# breakout.net
KiCad netlist of a schematic drawn in Altium Designer
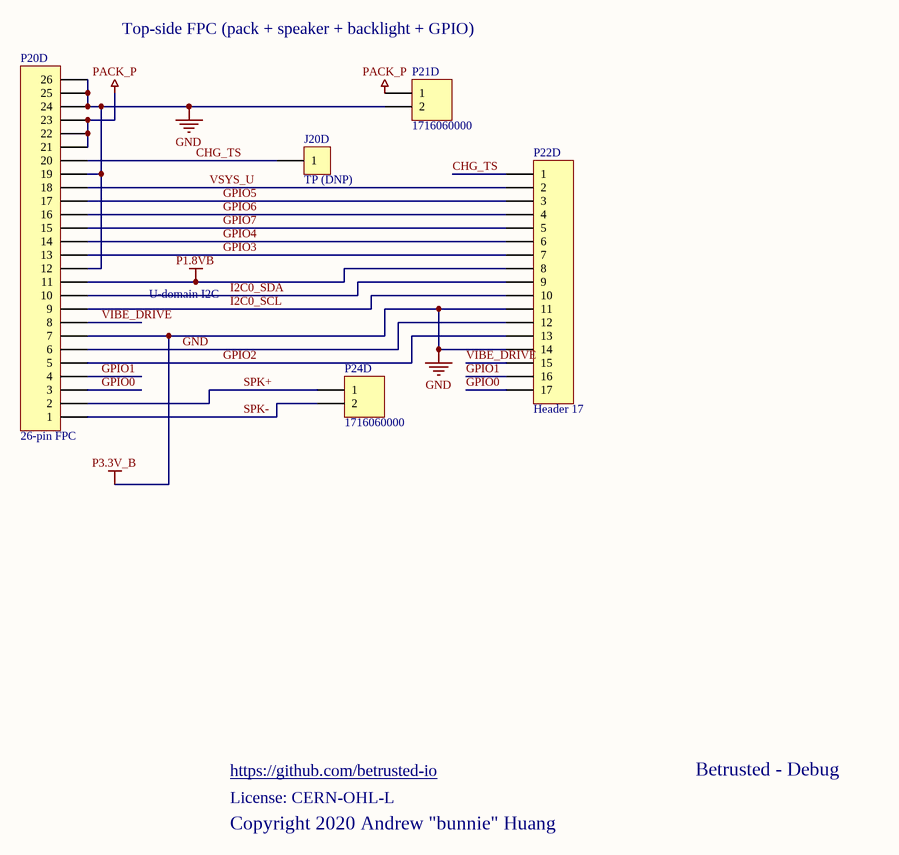
[diagram p0: breakout.SchDoc]

(export (version "E")
  (design (tool "Eeschema 10.0.6"))
  (components
    (comp (ref "J20D")
      (value "TP (DNP)")
      (footprint "RESTAP-0603")
      (description "Connector")
      (fields (field (name "MPN") "DNP"))
      (libsource (lib "*") (part "CON1"))
    )
    (comp (ref "P20D")
      (value "26-pin FPC")
      (footprint "HRS_FH34SRJ-26S-0.5SH(50)")
      (description "26 Pin FPC header")
      (fields (field (name "MPN") "FH34SRJ-26S-0.5SH(99)"))
      (libsource (lib "commonsch-new") (part "FPC-26"))
    )
    (comp (ref "P21D")
      (value "1716060000")
      (footprint "weidmuller_1716060000")
      (description "Header, 2-Pin")
      (fields (field (name "PUBLISHER") "Altium Limited"))
      (libsource (lib "Miscellaneous Connectors") (part "Header 2"))
    )
    (comp (ref "P22D")
      (value "Header 17")
      (footprint "HDR1X17")
      (description "Header, 17-Pin")
      (fields (field (name "PUBLISHER") "Altium Limited"))
      (libsource (lib "Miscellaneous Connectors") (part "Header 17"))
    )
    (comp (ref "P24D")
      (value "1716060000")
      (footprint "weidmuller_1716060000")
      (description "Header, 2-Pin")
      (fields (field (name "PUBLISHER") "Altium Limited"))
      (libsource (lib "Miscellaneous Connectors") (part "Header 2"))
    )
  )
  (nets
    (net (code "1") (name "/CHG_TS") (class "Default")
      (node (ref "J20D") (pin "1") (pinfunction "1_1") (pintype "passive"))
      (node (ref "P20D") (pin "20") (pinfunction "20_20") (pintype "passive"))
      (node (ref "P22D") (pin "1") (pinfunction "1_1") (pintype "passive"))
    )
    (net (code "2") (name "/GPIO0") (class "Default")
      (node (ref "P20D") (pin "3") (pinfunction "3_3") (pintype "passive"))
      (node (ref "P22D") (pin "17") (pinfunction "17_17") (pintype "passive"))
    )
    (net (code "3") (name "/GPIO1") (class "Default")
      (node (ref "P20D") (pin "4") (pinfunction "4_4") (pintype "passive"))
      (node (ref "P22D") (pin "16") (pinfunction "16_16") (pintype "passive"))
    )
    (net (code "4") (name "/GPIO2") (class "Default")
      (node (ref "P20D") (pin "5") (pinfunction "5_5") (pintype "passive"))
      (node (ref "P22D") (pin "13") (pinfunction "13_13") (pintype "passive"))
    )
    (net (code "5") (name "/GPIO3") (class "Default")
      (node (ref "P20D") (pin "13") (pinfunction "13_13") (pintype "passive"))
      (node (ref "P22D") (pin "7") (pinfunction "7_7") (pintype "passive"))
    )
    (net (code "6") (name "/GPIO4") (class "Default")
      (node (ref "P20D") (pin "14") (pinfunction "14_14") (pintype "passive"))
      (node (ref "P22D") (pin "6") (pinfunction "6_6") (pintype "passive"))
    )
    (net (code "7") (name "/GPIO5") (class "Default")
      (node (ref "P20D") (pin "17") (pinfunction "17_17") (pintype "passive"))
      (node (ref "P22D") (pin "3") (pinfunction "3_3") (pintype "passive"))
    )
    (net (code "8") (name "/GPIO6") (class "Default")
      (node (ref "P20D") (pin "16") (pinfunction "16_16") (pintype "passive"))
      (node (ref "P22D") (pin "4") (pinfunction "4_4") (pintype "passive"))
    )
    (net (code "9") (name "/GPIO7") (class "Default")
      (node (ref "P20D") (pin "15") (pinfunction "15_15") (pintype "passive"))
      (node (ref "P22D") (pin "5") (pinfunction "5_5") (pintype "passive"))
    )
    (net (code "10") (name "/I2C0_SCL") (class "Default")
      (node (ref "P20D") (pin "9") (pinfunction "9_9") (pintype "passive"))
      (node (ref "P22D") (pin "10") (pinfunction "10_10") (pintype "passive"))
    )
    (net (code "11") (name "/I2C0_SDA") (class "Default")
      (node (ref "P20D") (pin "10") (pinfunction "10_10") (pintype "passive"))
      (node (ref "P22D") (pin "9") (pinfunction "9_9") (pintype "passive"))
    )
    (net (code "12") (name "/SPK+") (class "Default")
      (node (ref "P20D") (pin "2") (pinfunction "2_2") (pintype "passive"))
      (node (ref "P24D") (pin "1") (pinfunction "1_1") (pintype "passive"))
    )
    (net (code "13") (name "/SPK-") (class "Default")
      (node (ref "P20D") (pin "1") (pinfunction "1_1") (pintype "passive"))
      (node (ref "P24D") (pin "2") (pinfunction "2_2") (pintype "passive"))
    )
    (net (code "14") (name "/VIBE_DRIVE") (class "Default")
      (node (ref "P20D") (pin "8") (pinfunction "8_8") (pintype "passive"))
      (node (ref "P22D") (pin "15") (pinfunction "15_15") (pintype "passive"))
    )
    (net (code "15") (name "/VSYS_U") (class "Default")
      (node (ref "P20D") (pin "18") (pinfunction "18_18") (pintype "passive"))
      (node (ref "P22D") (pin "2") (pinfunction "2_2") (pintype "passive"))
    )
    (net (code "16") (name "GND") (class "Default")
      (node (ref "P20D") (pin "12") (pinfunction "12_12") (pintype "passive"))
      (node (ref "P20D") (pin "19") (pinfunction "19_19") (pintype "passive"))
      (node (ref "P20D") (pin "24") (pinfunction "24_24") (pintype "passive"))
      (node (ref "P20D") (pin "25") (pinfunction "25_25") (pintype "passive"))
      (node (ref "P20D") (pin "26") (pinfunction "26_26") (pintype "passive"))
      (node (ref "P20D") (pin "6") (pinfunction "6_6") (pintype "passive"))
      (node (ref "P20D") (pin "7") (pinfunction "7_7") (pintype "passive"))
      (node (ref "P21D") (pin "2") (pinfunction "2_2") (pintype "passive"))
      (node (ref "P22D") (pin "11") (pinfunction "11_11") (pintype "passive"))
      (node (ref "P22D") (pin "12") (pinfunction "12_12") (pintype "passive"))
      (node (ref "P22D") (pin "14") (pinfunction "14_14") (pintype "passive"))
    )
    (net (code "17") (name "P1.8VB") (class "Default")
      (node (ref "P20D") (pin "11") (pinfunction "11_11") (pintype "passive"))
      (node (ref "P22D") (pin "8") (pinfunction "8_8") (pintype "passive"))
    )
    (net (code "18") (name "PACK_P") (class "Default")
      (node (ref "P20D") (pin "21") (pinfunction "21_21") (pintype "passive"))
      (node (ref "P20D") (pin "22") (pinfunction "22_22") (pintype "passive"))
      (node (ref "P20D") (pin "23") (pinfunction "23_23") (pintype "passive"))
      (node (ref "P21D") (pin "1") (pinfunction "1_1") (pintype "passive"))
    )
  )
)
